# trainiii_battery.net
KiCad netlist of a schematic drawn in EAGLE
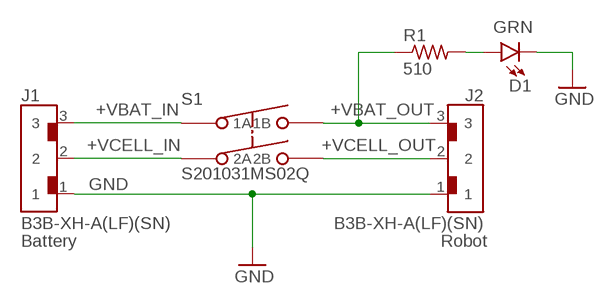
[diagram p0: schematic, sheet 1]

(export (version "E")
  (design (tool "Eeschema 10.0.6"))
  (components
    (comp (ref "D1")
      (value "GRN")
      (footprint "eagle-import:LED-0603")
      (libsource (lib "eagle-import") (part "LED0603"))
    )
    (comp (ref "J1")
      (value "B3B-XH-A(LF)(SN)")
      (footprint "eagle-import:B3B-XH-A(LF)(SN)")
      (libsource (lib "eagle-import") (part "B3B-XH-A(LF)(SN)"))
    )
    (comp (ref "J2")
      (value "B3B-XH-A(LF)(SN)")
      (footprint "eagle-import:B3B-XH-A(LF)(SN)")
      (libsource (lib "eagle-import") (part "B3B-XH-A(LF)(SN)"))
    )
    (comp (ref "R1")
      (value "510")
      (footprint "eagle-import:R0603")
      (libsource (lib "eagle-import") (part "R-US_R0603"))
    )
    (comp (ref "S1")
      (value "S201031MS02Q")
      (footprint "eagle-import:S201")
      (libsource (lib "eagle-import") (part "S201031MS02Q"))
    )
  )
  (nets
    (net (code "1") (name "/+VBAT_IN") (class "Default")
      (node (ref "J1") (pin "3") (pinfunction "3_3") (pintype "bidirectional"))
      (node (ref "S1") (pin "1") (pinfunction "1A_1") (pintype "input"))
    )
    (net (code "2") (name "/+VBAT_OUT") (class "Default")
      (node (ref "J2") (pin "3") (pinfunction "3_3") (pintype "bidirectional"))
      (node (ref "R1") (pin "1") (pinfunction "1_1") (pintype "passive"))
      (node (ref "S1") (pin "2") (pinfunction "1B_2") (pintype "output"))
    )
    (net (code "3") (name "/+VCELL_IN") (class "Default")
      (node (ref "J1") (pin "2") (pinfunction "2_2") (pintype "bidirectional"))
      (node (ref "S1") (pin "4") (pinfunction "2A_4") (pintype "input"))
    )
    (net (code "4") (name "/+VCELL_OUT") (class "Default")
      (node (ref "J2") (pin "2") (pinfunction "2_2") (pintype "bidirectional"))
      (node (ref "S1") (pin "5") (pinfunction "2B_5") (pintype "output"))
    )
    (net (code "5") (name "GND") (class "Default")
      (node (ref "D1") (pin "C") (pinfunction "C_C") (pintype "passive"))
      (node (ref "J1") (pin "1") (pinfunction "1_1") (pintype "bidirectional"))
      (node (ref "J2") (pin "1") (pinfunction "1_1") (pintype "bidirectional"))
    )
    (net (code "6") (name "Net-(D1-PadA)") (class "Default")
      (node (ref "D1") (pin "A") (pinfunction "A_A") (pintype "passive"))
      (node (ref "R1") (pin "2") (pinfunction "2_2") (pintype "passive"))
    )
  )
)
